# conn_usbc.net
KiCad netlist of a schematic drawn in Altium Designer
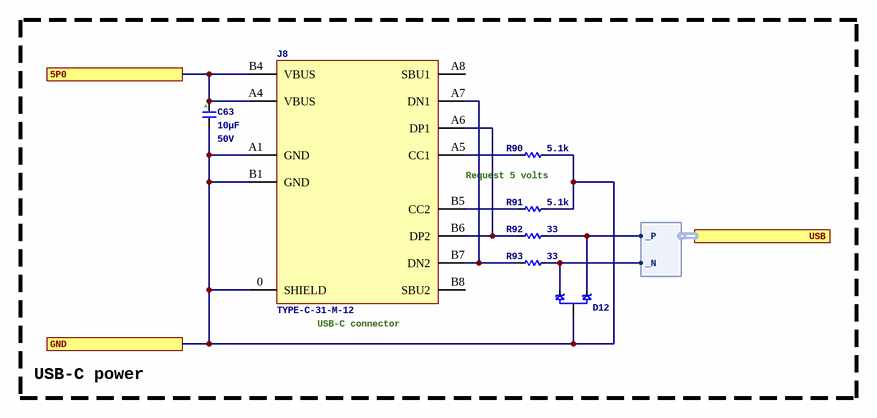
[diagram p0: conn_usbc.SchDoc]

(export (version "E")
  (design (tool "Eeschema 10.0.6"))
  (components
    (comp (ref "C63")
      (value "CGA5L1X7R1H106K160AC")
      (footprint "C1206_1.90MM")
      (description "CAP CER 10UF 50V X7R 1206")
      (fields
        (field (name "CAPACITANCE") "10µF")
        (field (name "VOLTAGE - RATED") "50V")
        (field (name "TOLERANCE") "±10%")
        (field (name "MANUFACTURER") "TDK Corporation")
      )
      (libsource (lib "sscp") (part "__template_cap_auto"))
    )
    (comp (ref "D12")
      (value "PESD2USB3UX")
      (footprint "3SOT23")
      (description "DIODE ESD USB SOT-23")
      (fields (field (name "MANUFACTURER") "Nexperia USA Inc."))
      (libsource (lib "SSCP") (part "TVS_PESD2USB3UX-T"))
    )
    (comp (ref "J8")
      (value "TYPE-C-31-M-12")
      (footprint "CONN_USBC_TYPE-C-31-M-12")
      (description "5A 1 16P Female Type-C SMD USB Connectors ROHS")
      (fields (field (name "MANUFACTURER") "HRO Electronics"))
      (libsource (lib "SSCP") (part "CONN_USBC_TYPE-C-31-M-12"))
    )
    (comp (ref "R90")
      (value "ERJ-2RKF5101X")
      (footprint "R0402_0.40MM")
      (description "RES SMD 5.1K OHM 1% 1/10W 0402")
      (fields
        (field (name "RESISTANCE") "5.1k")
        (field (name "TOLERANCE") "±1%")
        (field (name "MANUFACTURER") "Panasonic Electronic Components")
      )
      (libsource (lib "sscp") (part "__template_resistor"))
    )
    (comp (ref "R91")
      (value "ERJ-2RKF5101X")
      (footprint "R0402_0.40MM")
      (description "RES SMD 5.1K OHM 1% 1/10W 0402")
      (fields
        (field (name "RESISTANCE") "5.1k")
        (field (name "TOLERANCE") "±1%")
        (field (name "MANUFACTURER") "Panasonic Electronic Components")
      )
      (libsource (lib "sscp") (part "__template_resistor"))
    )
    (comp (ref "R92")
      (value "ERJ-2RKF33R0X")
      (footprint "R0402_0.40MM")
      (description "RES SMD 33 OHM 1% 1/10W 0402")
      (fields
        (field (name "RESISTANCE") "33")
        (field (name "TOLERANCE") "±1%")
        (field (name "MANUFACTURER") "Panasonic Electronic Components")
      )
      (libsource (lib "sscp") (part "__template_resistor"))
    )
    (comp (ref "R93")
      (value "ERJ-2RKF33R0X")
      (footprint "R0402_0.40MM")
      (description "RES SMD 33 OHM 1% 1/10W 0402")
      (fields
        (field (name "RESISTANCE") "33")
        (field (name "TOLERANCE") "±1%")
        (field (name "MANUFACTURER") "Panasonic Electronic Components")
      )
      (libsource (lib "sscp") (part "__template_resistor"))
    )
  )
  (nets
    (net (code "2") (name "/5P0") (class "Default")
      (node (ref "C63") (pin "1") (pintype "passive"))
      (node (ref "J8") (pin "A4") (pinfunction "VBUS_A4") (pintype "power_in"))
      (node (ref "J8") (pin "B4") (pinfunction "VBUS_B4") (pintype "passive"))
    )
    (net (code "3") (name "/GND") (class "Default")
      (node (ref "C63") (pin "2") (pintype "passive"))
      (node (ref "D12") (pin "3") (pintype "passive"))
      (node (ref "J8") (pin "0") (pinfunction "SHIELD_0") (pintype "power_in"))
      (node (ref "J8") (pin "A1") (pinfunction "GND_A1") (pintype "power_in"))
      (node (ref "J8") (pin "B1") (pinfunction "GND_B1") (pintype "power_in"))
      (node (ref "R90") (pin "1") (pintype "passive"))
      (node (ref "R91") (pin "1") (pintype "passive"))
    )
    (net (code "5") (name "Net-(D12-Pad1)") (class "Default")
      (node (ref "D12") (pin "1") (pintype "passive"))
      (node (ref "R92") (pin "1") (pintype "passive"))
    )
    (net (code "6") (name "Net-(D12-Pad2)") (class "Default")
      (node (ref "D12") (pin "2") (pintype "passive"))
      (node (ref "R93") (pin "1") (pintype "passive"))
    )
    (net (code "7") (name "Net-(J8-CC1)") (class "Default")
      (node (ref "J8") (pin "A5") (pinfunction "CC1_A5") (pintype "passive"))
      (node (ref "R90") (pin "2") (pintype "passive"))
    )
    (net (code "8") (name "Net-(J8-CC2)") (class "Default")
      (node (ref "J8") (pin "B5") (pinfunction "CC2_B5") (pintype "passive"))
      (node (ref "R91") (pin "2") (pintype "passive"))
    )
    (net (code "9") (name "Net-(J8-DN1)") (class "Default")
      (node (ref "J8") (pin "A7") (pinfunction "DN1_A7") (pintype "passive"))
      (node (ref "J8") (pin "B7") (pinfunction "DN2_B7") (pintype "passive"))
      (node (ref "R93") (pin "2") (pintype "passive"))
    )
    (net (code "10") (name "Net-(J8-DP1)") (class "Default")
      (node (ref "J8") (pin "A6") (pinfunction "DP1_A6") (pintype "passive"))
      (node (ref "J8") (pin "B6") (pinfunction "DP2_B6") (pintype "passive"))
      (node (ref "R92") (pin "2") (pintype "passive"))
    )
    (net (code "11") (name "unconnected-(J8-SBU1-PadA8)") (class "Default")
      (node (ref "J8") (pin "A8") (pinfunction "SBU1_A8") (pintype "passive"))
    )
    (net (code "12") (name "unconnected-(J8-SBU2-PadB8)") (class "Default")
      (node (ref "J8") (pin "B8") (pinfunction "SBU2_B8") (pintype "passive"))
    )
  )
)
